# 513.net
KiCad netlist of a schematic drawn in Altium Designer
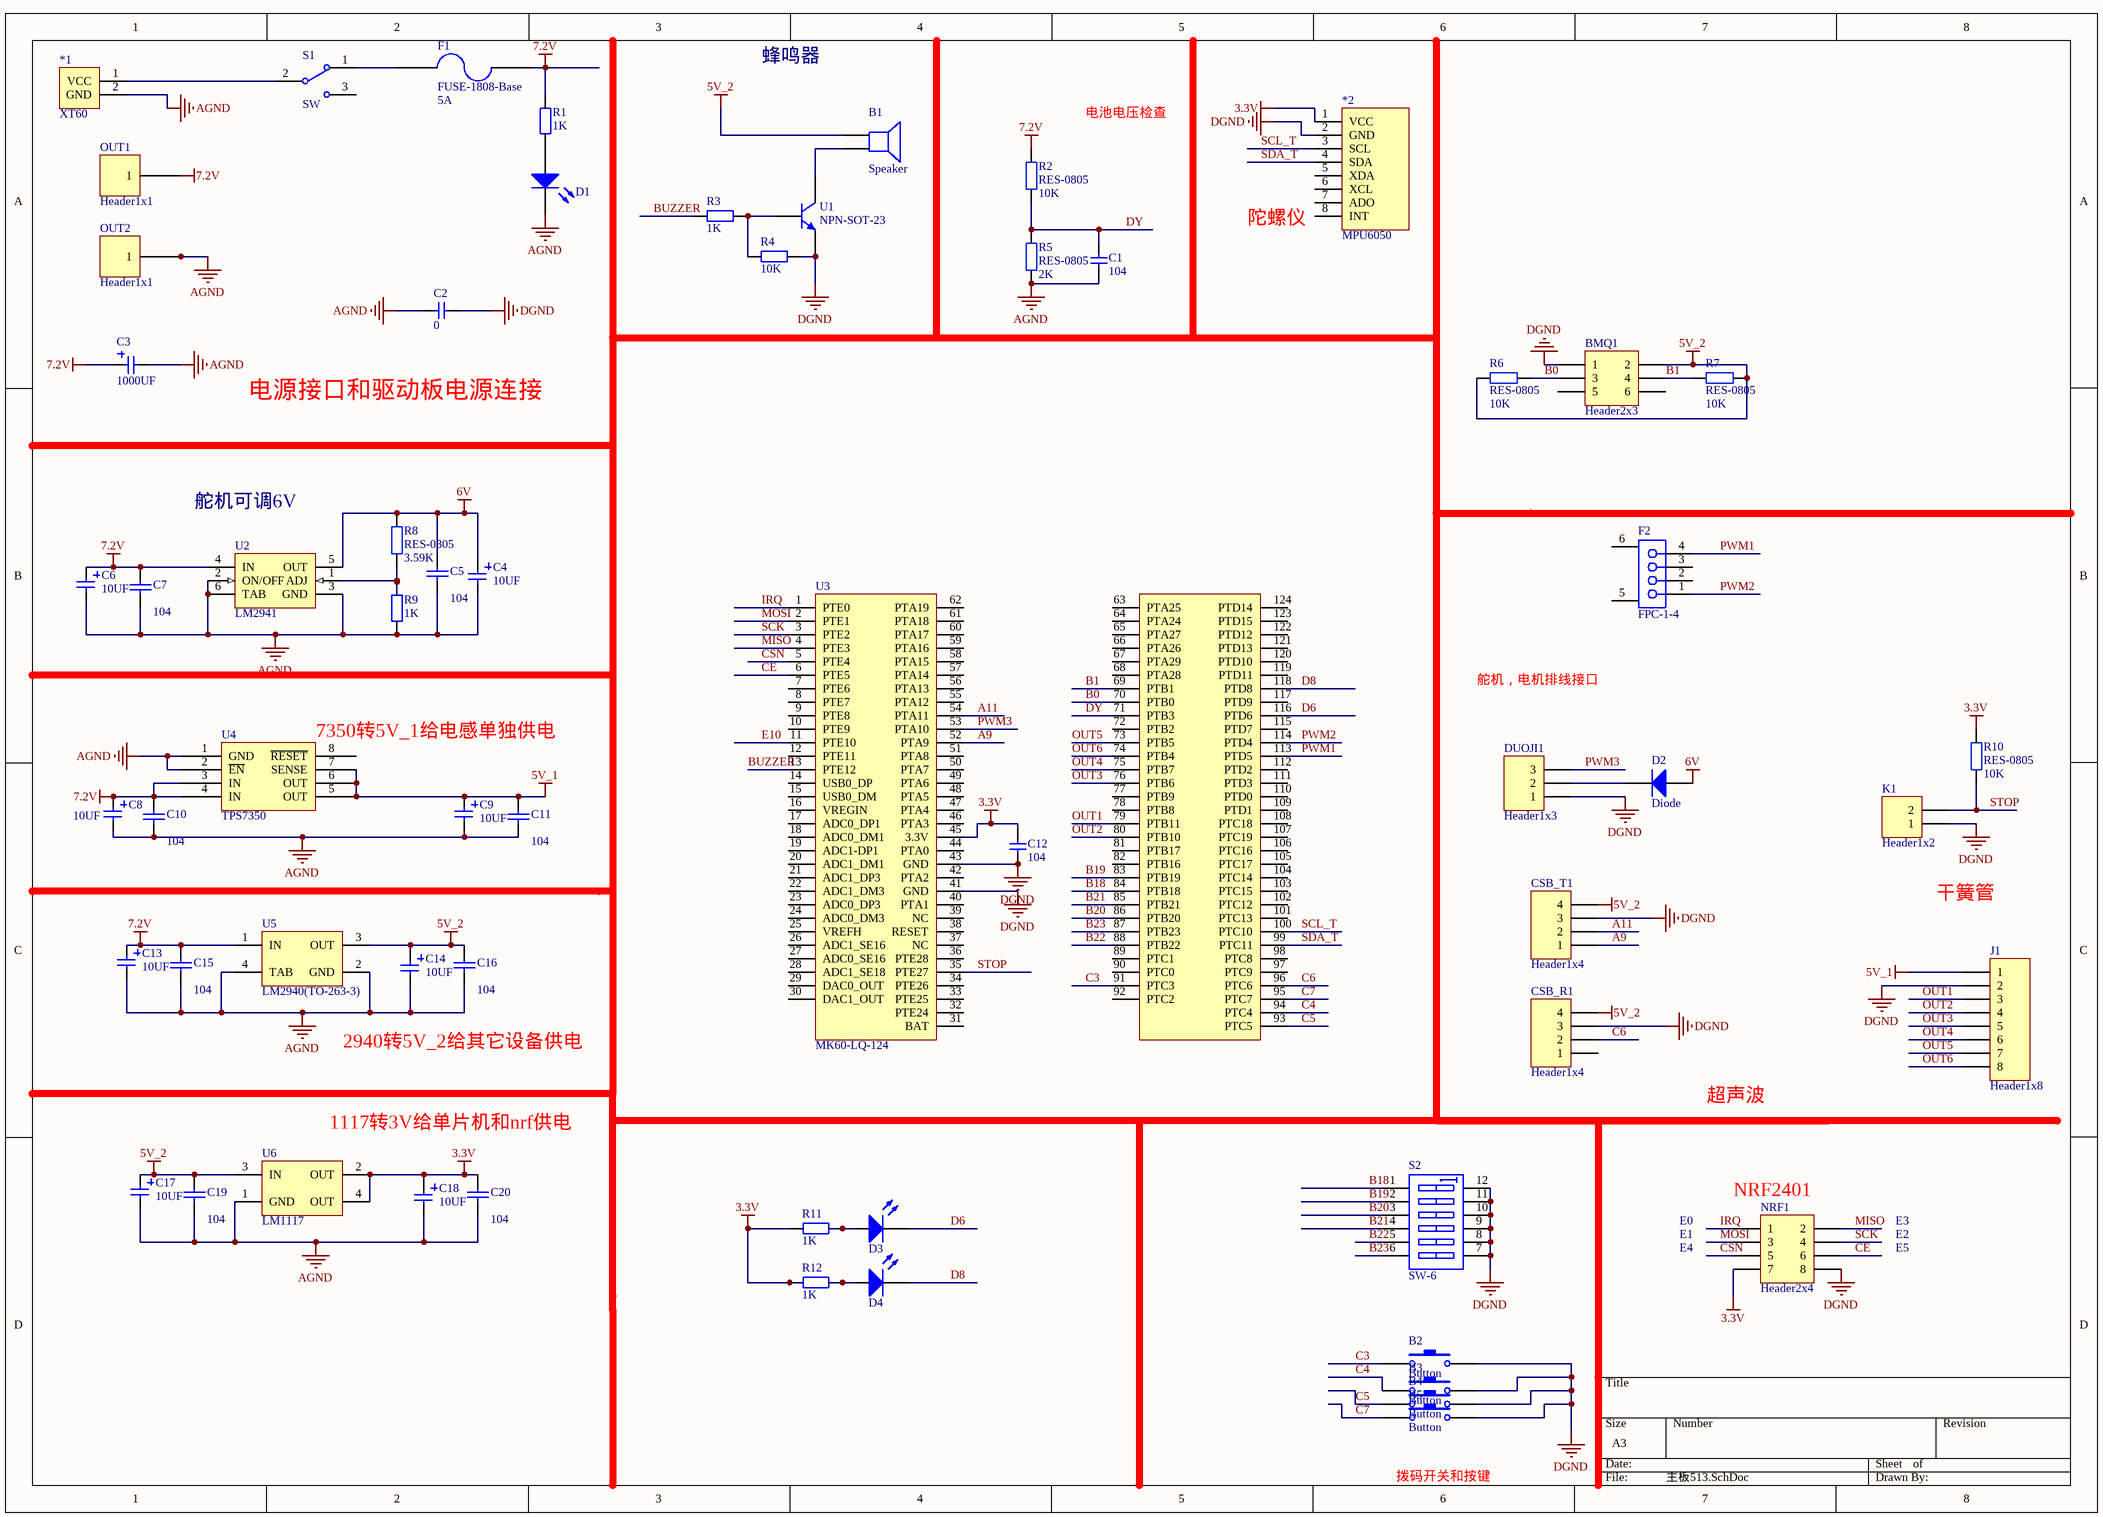
[diagram p0: 主板513.SchDoc]

(export (version "E")
  (design (tool "Eeschema 10.0.6"))
  (components
    (comp (ref "*1") (value "XT60") (footprint "XT60") (libsource (lib "信标主板") (part "XT60")))
    (comp (ref "*2") (value "MPU6050") (footprint "MPU6050") (libsource (lib "光电主板") (part "MPU6050")))
    (comp (ref "B1")
      (value "Speaker")
      (footprint "Beep")
      (description "Loudspeaker")
      (fields (field (name "PUBLISHER") "Altium Limited"))
      (libsource (lib "光电主板") (part "Speaker"))
    )
    (comp (ref "B2") (value "Button") (footprint "Button-SMT") (libsource (lib "Common_XJP") (part "Button")))
    (comp (ref "B3") (value "Button") (footprint "Button-SMT") (libsource (lib "Common_XJP") (part "Button")))
    (comp (ref "B4") (value "Button") (footprint "Button-SMT") (libsource (lib "Common_XJP") (part "Button")))
    (comp (ref "B5") (value "Button") (footprint "Button-SMT") (libsource (lib "Common_XJP") (part "Button")))
    (comp (ref "BMQ1")
      (value "Header2x3")
      (footprint "HEADER2X3")
      (libsource (lib "KING_Connector") (part "Header2x3"))
    )
    (comp (ref "C1")
      (value "CAP_0805")
      (footprint "C0805")
      (fields (field (name "ALTIUM_UNNAMED_1") "104"))
      (libsource (lib "主板2017") (part "CAP_0805"))
    )
    (comp (ref "C2")
      (value "CAP_0805")
      (footprint "C0805")
      (fields (field (name "ALTIUM_UNNAMED_1") "0"))
      (libsource (lib "KING_Common") (part "CAP_0805"))
    )
    (comp (ref "C3")
      (value "CAP_1000UF_DIP")
      (footprint "CAP_DIP_8×14")
      (fields (field (name "ALTIUM_UNNAMED_1") "1000UF"))
      (libsource (lib "KING_Common") (part "CAP_1000UF_DIP"))
    )
    (comp (ref "C4")
      (value "CAP_6032")
      (footprint "CAP_6032_C")
      (fields (field (name "ALTIUM_UNNAMED_1") "10UF"))
      (libsource (lib "KING_Common") (part "CAP_6032"))
    )
    (comp (ref "C5")
      (value "~")
      (footprint "CAP-0805")
      (fields (field (name "ALTIUM_UNNAMED_1") "104"))
      (libsource (lib "3.0Common_XJP") (part "CAP-0805(2012)"))
    )
    (comp (ref "C6")
      (value "CAP_6032")
      (footprint "CAP_6032_C")
      (fields (field (name "ALTIUM_UNNAMED_1") "10UF"))
      (libsource (lib "KING_Common") (part "CAP_6032"))
    )
    (comp (ref "C7")
      (value "~")
      (footprint "CAP-0805")
      (fields (field (name "ALTIUM_UNNAMED_1") "104"))
      (libsource (lib "3.0Common_XJP") (part "CAP-0805(2012)"))
    )
    (comp (ref "C8")
      (value "CAP_6032")
      (footprint "CAP_6032_C")
      (fields (field (name "ALTIUM_UNNAMED_1") "10UF"))
      (libsource (lib "KING_Common") (part "CAP_6032"))
    )
    (comp (ref "C9")
      (value "CAP_6032")
      (footprint "CAP_6032_C")
      (fields (field (name "ALTIUM_UNNAMED_1") "10UF"))
      (libsource (lib "KING_Common") (part "CAP_6032"))
    )
    (comp (ref "C10")
      (value "~")
      (footprint "CAP-0805")
      (fields (field (name "ALTIUM_UNNAMED_1") "104"))
      (libsource (lib "3.0Common_XJP") (part "CAP-0805(2012)"))
    )
    (comp (ref "C11")
      (value "~")
      (footprint "CAP-0805")
      (fields (field (name "ALTIUM_UNNAMED_1") "104"))
      (libsource (lib "3.0Common_XJP") (part "CAP-0805(2012)"))
    )
    (comp (ref "C12")
      (value "CAP_0805")
      (footprint "C0805")
      (fields (field (name "ALTIUM_UNNAMED_1") "104"))
      (libsource (lib "KING_Common") (part "CAP_0805"))
    )
    (comp (ref "C13")
      (value "CAP_6032")
      (footprint "CAP_6032_C")
      (fields (field (name "ALTIUM_UNNAMED_1") "10UF"))
      (libsource (lib "KING_Common") (part "CAP_6032"))
    )
    (comp (ref "C14")
      (value "CAP_6032")
      (footprint "CAP_6032_C")
      (fields (field (name "ALTIUM_UNNAMED_1") "10UF"))
      (libsource (lib "KING_Common") (part "CAP_6032"))
    )
    (comp (ref "C15")
      (value "~")
      (footprint "CAP-0805")
      (fields (field (name "ALTIUM_UNNAMED_1") "104"))
      (libsource (lib "3.0Common_XJP") (part "CAP-0805(2012)"))
    )
    (comp (ref "C16")
      (value "~")
      (footprint "CAP-0805")
      (fields (field (name "ALTIUM_UNNAMED_1") "104"))
      (libsource (lib "3.0Common_XJP") (part "CAP-0805(2012)"))
    )
    (comp (ref "C17")
      (value "CAP_6032")
      (footprint "CAP_6032_C")
      (fields (field (name "ALTIUM_UNNAMED_1") "10UF"))
      (libsource (lib "KING_Common") (part "CAP_6032"))
    )
    (comp (ref "C18")
      (value "CAP_6032")
      (footprint "CAP_6032_C")
      (fields (field (name "ALTIUM_UNNAMED_1") "10UF"))
      (libsource (lib "KING_Common") (part "CAP_6032"))
    )
    (comp (ref "C19")
      (value "~")
      (footprint "CAP-0805")
      (fields (field (name "ALTIUM_UNNAMED_1") "104"))
      (libsource (lib "3.0Common_XJP") (part "CAP-0805(2012)"))
    )
    (comp (ref "C20")
      (value "~")
      (footprint "CAP-0805")
      (fields (field (name "ALTIUM_UNNAMED_1") "104"))
      (libsource (lib "3.0Common_XJP") (part "CAP-0805(2012)"))
    )
    (comp (ref "CSB_R1")
      (value "Header1x4")
      (footprint "HEADER1X4")
      (libsource (lib "KING_Connector") (part "Header1x4"))
    )
    (comp (ref "CSB_T1")
      (value "Header1x4")
      (footprint "HEADER1X4")
      (libsource (lib "KING_Connector") (part "Header1x4"))
    )
    (comp (ref "D1")
      (value "LED_0805_R")
      (footprint "LED_0805_R")
      (libsource (lib "KING_Common") (part "LED_0805_R"))
    )
    (comp (ref "D2") (value "Diode") (footprint "DIODE") (libsource (lib "ZYF_Common") (part "Diode")))
    (comp (ref "D3")
      (value "LED_0805_R")
      (footprint "LED_0805_R")
      (libsource (lib "KING_Common") (part "LED_0805_R"))
    )
    (comp (ref "D4")
      (value "LED_0805_R")
      (footprint "LED_0805_R")
      (libsource (lib "KING_Common") (part "LED_0805_R"))
    )
    (comp (ref "DUOJI1")
      (value "Header1x3")
      (footprint "HEADER1X3")
      (libsource (lib "ZYF_Connector") (part "Header1x3"))
    )
    (comp (ref "F1")
      (value "FUSE-1808-Base")
      (footprint "Fuse1808_Base")
      (description "保险丝")
      (fields (field (name "ALTIUM_UNNAMED_1") "5A"))
      (libsource (lib "电机驱动") (part "FUSE-1808-Base"))
    )
    (comp (ref "F2")
      (value "FPC-1-4")
      (footprint "FPC-1-4")
      (libsource (lib "ZYF_Connector") (part "FPC-1-4"))
    )
    (comp (ref "J1")
      (value "Header1x8")
      (footprint "HEADER1X8")
      (libsource (lib "KING_Connector") (part "Header1x8"))
    )
    (comp (ref "K1")
      (value "Header1x2")
      (footprint "HEADER1X2")
      (libsource (lib "KING_Connector") (part "Header1x2"))
    )
    (comp (ref "NRF1")
      (value "Header2x4")
      (footprint "HEADER2X4")
      (libsource (lib "KING_Connector") (part "Header2x4"))
    )
    (comp (ref "OUT1")
      (value "Header1x1")
      (footprint "HEADER1X1")
      (libsource (lib "ZZY_connector") (part "Header1x1"))
    )
    (comp (ref "OUT2")
      (value "Header1x1")
      (footprint "HEADER1X1")
      (libsource (lib "ZZY_connector") (part "Header1x1"))
    )
    (comp (ref "R1")
      (value "RES")
      (footprint "R0805")
      (fields (field (name "ALTIUM_UNNAMED_1") "1K"))
      (libsource (lib "KING_Common") (part "RES"))
    )
    (comp (ref "R2")
      (value "RES-0805")
      (footprint "RES-0805")
      (fields (field (name "ALTIUM_UNNAMED_1") "10K"))
      (libsource (lib "主板2017") (part "RES-0805"))
    )
    (comp (ref "R3")
      (value "RES")
      (footprint "R0805")
      (fields (field (name "ALTIUM_UNNAMED_1") "1K"))
      (libsource (lib "KING_Common") (part "RES"))
    )
    (comp (ref "R4")
      (value "RES")
      (footprint "R0805")
      (fields (field (name "ALTIUM_UNNAMED_1") "10K"))
      (libsource (lib "KING_Common") (part "RES"))
    )
    (comp (ref "R5")
      (value "RES-0805")
      (footprint "RES-0805")
      (fields (field (name "ALTIUM_UNNAMED_1") "2K"))
      (libsource (lib "主板2017") (part "RES-0805"))
    )
    (comp (ref "R6")
      (value "RES-0805")
      (footprint "RES-0805")
      (fields (field (name "ALTIUM_UNNAMED_1") "10K"))
      (libsource (lib "Common_XJP") (part "RES-0805"))
    )
    (comp (ref "R7")
      (value "RES-0805")
      (footprint "RES-0805")
      (fields (field (name "ALTIUM_UNNAMED_1") "10K"))
      (libsource (lib "Common_XJP") (part "RES-0805"))
    )
    (comp (ref "R8")
      (value "RES-0805")
      (footprint "RES-0805")
      (fields (field (name "ALTIUM_UNNAMED_1") "3.59K"))
      (libsource (lib "TQH_common") (part "RES-0805"))
    )
    (comp (ref "R9")
      (value "RES")
      (footprint "R0805")
      (fields (field (name "ALTIUM_UNNAMED_1") "1K"))
      (libsource (lib "KING_Common") (part "RES"))
    )
    (comp (ref "R10")
      (value "RES-0805")
      (footprint "RES-0805")
      (fields (field (name "ALTIUM_UNNAMED_1") "10K"))
      (libsource (lib "Common_XJP") (part "RES-0805"))
    )
    (comp (ref "R11")
      (value "RES")
      (footprint "R0805")
      (fields (field (name "ALTIUM_UNNAMED_1") "1K"))
      (libsource (lib "KING_Common") (part "RES"))
    )
    (comp (ref "R12")
      (value "RES")
      (footprint "R0805")
      (fields (field (name "ALTIUM_UNNAMED_1") "1K"))
      (libsource (lib "KING_Common") (part "RES"))
    )
    (comp (ref "S1") (value "SW") (footprint "SW-B") (libsource (lib "Common_XJP") (part "SW")))
    (comp (ref "S2") (value "SW-6") (footprint "SW-SMT-12") (libsource (lib "Common_XJP") (part "SW-6")))
    (comp (ref "U1")
      (value "NPN-SOT-23")
      (footprint "SOT-23")
      (libsource (lib "Common_XJP") (part "NPN-SOT-23"))
    )
    (comp (ref "U2") (value "LM2941") (footprint "TO-263-5S") (libsource (lib "KING_IC") (part "LM2941")))
    (comp (ref "U3")
      (value "MK60-LQ-124")
      (footprint "MK60-LQ-144")
      (libsource (lib "IC_XJP") (part "MK60-LQ-124"))
    )
    (comp (ref "U4") (value "TPS7350") (footprint "SOP-8") (libsource (lib "ZYF_IC") (part "TPS7350")))
    (comp (ref "U5")
      (value "LM2940(TO-263-3)")
      (footprint "TO-263-3")
      (libsource (lib "ZYF_IC") (part "LM2940(TO-263-3)"))
    )
    (comp (ref "U6")
      (value "LM1117")
      (footprint "SOT-223")
      (libsource (lib "KING_IC") (part "LM1117_SOT_223"))
    )
  )
  (nets
    (net (code "1") (name "/A9") (class "Default")
      (node (ref "CSB_T1") (pin "1") (pinfunction "1_1") (pintype "passive"))
      (node (ref "U3") (pin "52") (pinfunction "PTA9_52") (pintype "passive"))
    )
    (net (code "2") (name "/A11") (class "Default")
      (node (ref "CSB_T1") (pin "2") (pinfunction "2_2") (pintype "passive"))
      (node (ref "U3") (pin "54") (pinfunction "PTA11_54") (pintype "passive"))
    )
    (net (code "3") (name "/B0") (class "Default")
      (node (ref "BMQ1") (pin "3") (pinfunction "3_3") (pintype "passive"))
      (node (ref "R6") (pin "2") (pinfunction "2_2") (pintype "passive"))
      (node (ref "U3") (pin "70") (pinfunction "PTB0_70") (pintype "passive"))
    )
    (net (code "4") (name "/B1") (class "Default")
      (node (ref "BMQ1") (pin "4") (pinfunction "4_4") (pintype "passive"))
      (node (ref "R7") (pin "1") (pinfunction "1_1") (pintype "passive"))
      (node (ref "U3") (pin "69") (pinfunction "PTB1_69") (pintype "passive"))
    )
    (net (code "5") (name "/B18") (class "Default")
      (node (ref "S2") (pin "1") (pinfunction "A1_1") (pintype "passive"))
      (node (ref "U3") (pin "84") (pinfunction "PTB18_84") (pintype "passive"))
    )
    (net (code "6") (name "/B19") (class "Default")
      (node (ref "S2") (pin "2") (pinfunction "A2_2") (pintype "passive"))
      (node (ref "U3") (pin "83") (pinfunction "PTB19_83") (pintype "passive"))
    )
    (net (code "7") (name "/B20") (class "Default")
      (node (ref "S2") (pin "3") (pinfunction "A3_3") (pintype "passive"))
      (node (ref "U3") (pin "86") (pinfunction "PTB20_86") (pintype "passive"))
    )
    (net (code "8") (name "/B21") (class "Default")
      (node (ref "S2") (pin "4") (pinfunction "A4_4") (pintype "passive"))
      (node (ref "U3") (pin "85") (pinfunction "PTB21_85") (pintype "passive"))
    )
    (net (code "9") (name "/B22") (class "Default")
      (node (ref "S2") (pin "5") (pinfunction "A5_5") (pintype "passive"))
      (node (ref "U3") (pin "88") (pinfunction "PTB22_88") (pintype "passive"))
    )
    (net (code "10") (name "/B23") (class "Default")
      (node (ref "S2") (pin "6") (pinfunction "A6_6") (pintype "passive"))
      (node (ref "U3") (pin "87") (pinfunction "PTB23_87") (pintype "passive"))
    )
    (net (code "11") (name "/BUZZER") (class "Default")
      (node (ref "R3") (pin "1") (pinfunction "1_1") (pintype "passive"))
      (node (ref "U3") (pin "13") (pinfunction "PTE12_13") (pintype "passive"))
    )
    (net (code "12") (name "/C3") (class "Default")
      (node (ref "B2") (pin "1") (pinfunction "1_1") (pintype "passive"))
      (node (ref "U3") (pin "91") (pinfunction "PTC3_91") (pintype "passive"))
    )
    (net (code "13") (name "/C4") (class "Default")
      (node (ref "B3") (pin "1") (pinfunction "1_1") (pintype "passive"))
      (node (ref "U3") (pin "94") (pinfunction "PTC4_94") (pintype "passive"))
    )
    (net (code "14") (name "/C5") (class "Default")
      (node (ref "B4") (pin "1") (pinfunction "1_1") (pintype "passive"))
      (node (ref "U3") (pin "93") (pinfunction "PTC5_93") (pintype "passive"))
    )
    (net (code "15") (name "/C6") (class "Default")
      (node (ref "CSB_R1") (pin "2") (pinfunction "2_2") (pintype "passive"))
      (node (ref "U3") (pin "96") (pinfunction "PTC6_96") (pintype "passive"))
    )
    (net (code "16") (name "/C7") (class "Default")
      (node (ref "B5") (pin "1") (pinfunction "1_1") (pintype "passive"))
      (node (ref "U3") (pin "95") (pinfunction "PTC7_95") (pintype "passive"))
    )
    (net (code "17") (name "/CE") (class "Default")
      (node (ref "NRF1") (pin "6") (pinfunction "6_6") (pintype "passive"))
      (node (ref "U3") (pin "6") (pinfunction "PTE5_6") (pintype "passive"))
    )
    (net (code "18") (name "/CSN") (class "Default")
      (node (ref "NRF1") (pin "5") (pinfunction "5_5") (pintype "passive"))
      (node (ref "U3") (pin "5") (pinfunction "PTE4_5") (pintype "passive"))
    )
    (net (code "19") (name "/D6") (class "Default")
      (node (ref "D3") (pin "2") (pinfunction "K_2") (pintype "passive"))
      (node (ref "U3") (pin "116") (pinfunction "PTD6_116") (pintype "passive"))
    )
    (net (code "20") (name "/D8") (class "Default")
      (node (ref "D4") (pin "2") (pinfunction "K_2") (pintype "passive"))
      (node (ref "U3") (pin "118") (pinfunction "PTD8_118") (pintype "passive"))
    )
    (net (code "21") (name "/DY") (class "Default")
      (node (ref "C1") (pin "2") (pinfunction "2_2") (pintype "passive"))
      (node (ref "R2") (pin "1") (pinfunction "1_1") (pintype "passive"))
      (node (ref "R5") (pin "2") (pinfunction "2_2") (pintype "passive"))
      (node (ref "U3") (pin "71") (pinfunction "PTB3_71") (pintype "passive"))
    )
    (net (code "22") (name "/E10") (class "Default")
      (node (ref "U3") (pin "11") (pinfunction "PTE10_11") (pintype "passive"))
    )
    (net (code "23") (name "/IRQ") (class "Default")
      (node (ref "NRF1") (pin "1") (pinfunction "1_1") (pintype "passive"))
      (node (ref "U3") (pin "1") (pinfunction "PTE0_1") (pintype "passive"))
    )
    (net (code "24") (name "/MISO") (class "Default")
      (node (ref "NRF1") (pin "2") (pinfunction "2_2") (pintype "passive"))
      (node (ref "U3") (pin "4") (pinfunction "PTE3_4") (pintype "passive"))
    )
    (net (code "25") (name "/MOSI") (class "Default")
      (node (ref "NRF1") (pin "3") (pinfunction "3_3") (pintype "passive"))
      (node (ref "U3") (pin "2") (pinfunction "PTE1_2") (pintype "passive"))
    )
    (net (code "26") (name "/OUT1") (class "Default")
      (node (ref "J1") (pin "3") (pinfunction "3_3") (pintype "passive"))
      (node (ref "U3") (pin "79") (pinfunction "PTB11_79") (pintype "passive"))
    )
    (net (code "27") (name "/OUT2") (class "Default")
      (node (ref "J1") (pin "4") (pinfunction "4_4") (pintype "passive"))
      (node (ref "U3") (pin "80") (pinfunction "PTB10_80") (pintype "passive"))
    )
    (net (code "28") (name "/OUT3") (class "Default")
      (node (ref "J1") (pin "5") (pinfunction "5_5") (pintype "passive"))
      (node (ref "U3") (pin "76") (pinfunction "PTB6_76") (pintype "passive"))
    )
    (net (code "29") (name "/OUT4") (class "Default")
      (node (ref "J1") (pin "6") (pinfunction "6_6") (pintype "passive"))
      (node (ref "U3") (pin "75") (pinfunction "PTB7_75") (pintype "passive"))
    )
    (net (code "30") (name "/OUT5") (class "Default")
      (node (ref "J1") (pin "7") (pinfunction "7_7") (pintype "passive"))
      (node (ref "U3") (pin "73") (pinfunction "PTB5_73") (pintype "passive"))
    )
    (net (code "31") (name "/OUT6") (class "Default")
      (node (ref "J1") (pin "8") (pinfunction "8_8") (pintype "passive"))
      (node (ref "U3") (pin "74") (pinfunction "PTB4_74") (pintype "passive"))
    )
    (net (code "32") (name "/PWM1") (class "Default")
      (node (ref "F2") (pin "4") (pinfunction "4_4") (pintype "passive"))
      (node (ref "U3") (pin "113") (pinfunction "PTD5_113") (pintype "passive"))
    )
    (net (code "33") (name "/PWM2") (class "Default")
      (node (ref "F2") (pin "1") (pinfunction "1_1") (pintype "passive"))
      (node (ref "U3") (pin "114") (pinfunction "PTD4_114") (pintype "passive"))
    )
    (net (code "34") (name "/PWM3") (class "Default")
      (node (ref "DUOJI1") (pin "3") (pinfunction "3_3") (pintype "passive"))
      (node (ref "U3") (pin "53") (pinfunction "PTA10_53") (pintype "passive"))
    )
    (net (code "35") (name "/SCK") (class "Default")
      (node (ref "NRF1") (pin "4") (pinfunction "4_4") (pintype "passive"))
      (node (ref "U3") (pin "3") (pinfunction "PTE2_3") (pintype "passive"))
    )
    (net (code "36") (name "/SCL_T") (class "Default")
      (node (ref "*2") (pin "3") (pinfunction "SCL_3") (pintype "passive"))
      (node (ref "U3") (pin "100") (pinfunction "PTC10_100") (pintype "passive"))
    )
    (net (code "37") (name "/SDA_T") (class "Default")
      (node (ref "*2") (pin "4") (pinfunction "SDA_4") (pintype "passive"))
      (node (ref "U3") (pin "99") (pinfunction "PTC11_99") (pintype "passive"))
    )
    (net (code "38") (name "/STOP") (class "Default")
      (node (ref "K1") (pin "2") (pinfunction "2_2") (pintype "passive"))
      (node (ref "R10") (pin "1") (pinfunction "1_1") (pintype "passive"))
      (node (ref "U3") (pin "35") (pinfunction "PTE27_35") (pintype "passive"))
    )
    (net (code "39") (name "3.3V") (class "Default")
      (node (ref "*2") (pin "1") (pinfunction "VCC_1") (pintype "passive"))
      (node (ref "C12") (pin "2") (pinfunction "2_2") (pintype "passive"))
      (node (ref "C18") (pin "1") (pinfunction "1_1") (pintype "passive"))
      (node (ref "C20") (pin "2") (pinfunction "2_2") (pintype "passive"))
      (node (ref "NRF1") (pin "7") (pinfunction "7_7") (pintype "passive"))
      (node (ref "R10") (pin "2") (pinfunction "2_2") (pintype "passive"))
      (node (ref "R11") (pin "1") (pinfunction "1_1") (pintype "passive"))
      (node (ref "R12") (pin "1") (pinfunction "1_1") (pintype "passive"))
      (node (ref "U3") (pin "45") (pinfunction "3.3V_45") (pintype "passive"))
      (node (ref "U6") (pin "2") (pinfunction "OUT_2") (pintype "power_in"))
      (node (ref "U6") (pin "4") (pinfunction "OUT_4") (pintype "power_in"))
    )
    (net (code "40") (name "5V_1") (class "Default")
      (node (ref "C11") (pin "2") (pinfunction "2_2") (pintype "passive"))
      (node (ref "C9") (pin "1") (pinfunction "1_1") (pintype "passive"))
      (node (ref "J1") (pin "1") (pinfunction "1_1") (pintype "passive"))
      (node (ref "U4") (pin "5") (pinfunction "OUT_5") (pintype "passive"))
      (node (ref "U4") (pin "6") (pinfunction "OUT_6") (pintype "passive"))
      (node (ref "U4") (pin "7") (pinfunction "SENSE_7") (pintype "passive"))
    )
    (net (code "41") (name "5V_2") (class "Default")
      (node (ref "B1") (pin "1") (pinfunction "1_1") (pintype "passive"))
      (node (ref "BMQ1") (pin "2") (pinfunction "2_2") (pintype "passive"))
      (node (ref "C14") (pin "1") (pinfunction "1_1") (pintype "passive"))
      (node (ref "C16") (pin "2") (pinfunction "2_2") (pintype "passive"))
      (node (ref "C17") (pin "1") (pinfunction "1_1") (pintype "passive"))
      (node (ref "C19") (pin "2") (pinfunction "2_2") (pintype "passive"))
      (node (ref "CSB_R1") (pin "4") (pinfunction "4_4") (pintype "passive"))
      (node (ref "CSB_T1") (pin "4") (pinfunction "4_4") (pintype "passive"))
      (node (ref "R6") (pin "1") (pinfunction "1_1") (pintype "passive"))
      (node (ref "R7") (pin "2") (pinfunction "2_2") (pintype "passive"))
      (node (ref "U5") (pin "3") (pinfunction "OUT_3") (pintype "power_in"))
      (node (ref "U6") (pin "3") (pinfunction "IN_3") (pintype "power_in"))
    )
    (net (code "42") (name "6V") (class "Default")
      (node (ref "C4") (pin "1") (pinfunction "1_1") (pintype "passive"))
      (node (ref "C5") (pin "2") (pinfunction "2_2") (pintype "passive"))
      (node (ref "D2") (pin "1") (pinfunction "A_1") (pintype "passive"))
      (node (ref "R8") (pin "1") (pinfunction "1_1") (pintype "passive"))
      (node (ref "U2") (pin "5") (pinfunction "OUT_5") (pintype "power_in"))
    )
    (net (code "43") (name "7.2V") (class "Default")
      (node (ref "C10") (pin "2") (pinfunction "2_2") (pintype "passive"))
      (node (ref "C13") (pin "1") (pinfunction "1_1") (pintype "passive"))
      (node (ref "C15") (pin "2") (pinfunction "2_2") (pintype "passive"))
      (node (ref "C3") (pin "1") (pinfunction "1_1") (pintype "passive"))
      (node (ref "C6") (pin "1") (pinfunction "1_1") (pintype "passive"))
      (node (ref "C7") (pin "2") (pinfunction "2_2") (pintype "passive"))
      (node (ref "C8") (pin "1") (pinfunction "1_1") (pintype "passive"))
      (node (ref "F1") (pin "2") (pinfunction "2_2") (pintype "passive"))
      (node (ref "OUT1") (pin "1") (pinfunction "1_1") (pintype "passive"))
      (node (ref "R1") (pin "1") (pinfunction "1_1") (pintype "passive"))
      (node (ref "R2") (pin "2") (pinfunction "2_2") (pintype "passive"))
      (node (ref "U2") (pin "4") (pinfunction "IN_4") (pintype "power_in"))
      (node (ref "U4") (pin "3") (pinfunction "IN_3") (pintype "passive"))
      (node (ref "U4") (pin "4") (pinfunction "IN_4") (pintype "passive"))
      (node (ref "U5") (pin "1") (pinfunction "IN_1") (pintype "power_in"))
    )
    (net (code "44") (name "AGND") (class "Default")
      (node (ref "*1") (pin "2") (pinfunction "GND_2") (pintype "passive"))
      (node (ref "C1") (pin "1") (pinfunction "1_1") (pintype "passive"))
      (node (ref "C10") (pin "1") (pinfunction "1_1") (pintype "passive"))
      (node (ref "C11") (pin "1") (pinfunction "1_1") (pintype "passive"))
      (node (ref "C13") (pin "2") (pinfunction "2_2") (pintype "passive"))
      (node (ref "C14") (pin "2") (pinfunction "2_2") (pintype "passive"))
      (node (ref "C15") (pin "1") (pinfunction "1_1") (pintype "passive"))
      (node (ref "C16") (pin "1") (pinfunction "1_1") (pintype "passive"))
      (node (ref "C17") (pin "2") (pinfunction "2_2") (pintype "passive"))
      (node (ref "C18") (pin "2") (pinfunction "2_2") (pintype "passive"))
      (node (ref "C19") (pin "1") (pinfunction "1_1") (pintype "passive"))
      (node (ref "C2") (pin "2") (pinfunction "2_2") (pintype "passive"))
      (node (ref "C20") (pin "1") (pinfunction "1_1") (pintype "passive"))
      (node (ref "C3") (pin "2") (pinfunction "2_2") (pintype "passive"))
      (node (ref "C4") (pin "2") (pinfunction "2_2") (pintype "passive"))
      (node (ref "C5") (pin "1") (pinfunction "1_1") (pintype "passive"))
      (node (ref "C6") (pin "2") (pinfunction "2_2") (pintype "passive"))
      (node (ref "C7") (pin "1") (pinfunction "1_1") (pintype "passive"))
      (node (ref "C8") (pin "2") (pinfunction "2_2") (pintype "passive"))
      (node (ref "C9") (pin "2") (pinfunction "2_2") (pintype "passive"))
      (node (ref "D1") (pin "2") (pinfunction "K_2") (pintype "passive"))
      (node (ref "OUT2") (pin "1") (pinfunction "1_1") (pintype "passive"))
      (node (ref "R5") (pin "1") (pinfunction "1_1") (pintype "passive"))
      (node (ref "R9") (pin "1") (pinfunction "1_1") (pintype "passive"))
      (node (ref "U2") (pin "2") (pinfunction "ON/OFF_2") (pintype "input"))
      (node (ref "U2") (pin "3") (pinfunction "GND_3") (pintype "power_in"))
      (node (ref "U2") (pin "6") (pinfunction "TAB_6") (pintype "power_in"))
      (node (ref "U4") (pin "1") (pinfunction "GND_1") (pintype "passive"))
      (node (ref "U4") (pin "2") (pinfunction "~{EN}_2") (pintype "passive"))
      (node (ref "U5") (pin "2") (pinfunction "GND_2") (pintype "power_in"))
      (node (ref "U5") (pin "4") (pinfunction "TAB_4") (pintype "power_in"))
      (node (ref "U6") (pin "1") (pinfunction "GND_1") (pintype "power_in"))
    )
    (net (code "45") (name "DGND") (class "Default")
      (node (ref "*2") (pin "2") (pinfunction "GND_2") (pintype "passive"))
      (node (ref "B2") (pin "2") (pinfunction "2_2") (pintype "passive"))
      (node (ref "B3") (pin "2") (pinfunction "2_2") (pintype "passive"))
      (node (ref "B4") (pin "2") (pinfunction "2_2") (pintype "passive"))
      (node (ref "B5") (pin "2") (pinfunction "2_2") (pintype "passive"))
      (node (ref "BMQ1") (pin "1") (pinfunction "1_1") (pintype "passive"))
      (node (ref "C12") (pin "1") (pinfunction "1_1") (pintype "passive"))
      (node (ref "C2") (pin "1") (pinfunction "1_1") (pintype "passive"))
      (node (ref "CSB_R1") (pin "3") (pinfunction "3_3") (pintype "passive"))
      (node (ref "CSB_T1") (pin "3") (pinfunction "3_3") (pintype "passive"))
      (node (ref "DUOJI1") (pin "1") (pinfunction "1_1") (pintype "passive"))
      (node (ref "J1") (pin "2") (pinfunction "2_2") (pintype "passive"))
      (node (ref "K1") (pin "1") (pinfunction "1_1") (pintype "passive"))
      (node (ref "NRF1") (pin "8") (pinfunction "8_8") (pintype "passive"))
      (node (ref "R4") (pin "2") (pinfunction "2_2") (pintype "passive"))
      (node (ref "S2") (pin "10") (pinfunction "B3_10") (pintype "passive"))
      (node (ref "S2") (pin "11") (pinfunction "B2_11") (pintype "passive"))
      (node (ref "S2") (pin "12") (pinfunction "B1_12") (pintype "passive"))
      (node (ref "S2") (pin "7") (pinfunction "B6_7") (pintype "passive"))
      (node (ref "S2") (pin "8") (pinfunction "B5_8") (pintype "passive"))
      (node (ref "S2") (pin "9") (pinfunction "B4_9") (pintype "passive"))
      (node (ref "U1") (pin "1") (pinfunction "E_1") (pintype "passive"))
      (node (ref "U3") (pin "41") (pinfunction "GND_41") (pintype "passive"))
      (node (ref "U3") (pin "43") (pinfunction "GND_43") (pintype "passive"))
    )
    (net (code "46") (name "Net-(*1-VCC)") (class "Default")
      (node (ref "*1") (pin "1") (pinfunction "VCC_1") (pintype "passive"))
      (node (ref "S1") (pin "2") (pinfunction "2_2") (pintype "passive"))
    )
    (net (code "47") (name "Net-(D1-A)") (class "Default")
      (node (ref "D1") (pin "1") (pinfunction "A_1") (pintype "passive"))
      (node (ref "R1") (pin "2") (pinfunction "2_2") (pintype "passive"))
    )
    (net (code "48") (name "Net-(D2-K)") (class "Default")
      (node (ref "D2") (pin "2") (pinfunction "K_2") (pintype "passive"))
      (node (ref "DUOJI1") (pin "2") (pinfunction "2_2") (pintype "passive"))
    )
    (net (code "49") (name "Net-(D3-A)") (class "Default")
      (node (ref "D3") (pin "1") (pinfunction "A_1") (pintype "passive"))
      (node (ref "R11") (pin "2") (pinfunction "2_2") (pintype "passive"))
    )
    (net (code "50") (name "Net-(D4-A)") (class "Default")
      (node (ref "D4") (pin "1") (pinfunction "A_1") (pintype "passive"))
      (node (ref "R12") (pin "2") (pinfunction "2_2") (pintype "passive"))
    )
    (net (code "51") (name "Net-(F1-Pad1)") (class "Default")
      (node (ref "F1") (pin "1") (pinfunction "1_1") (pintype "passive"))
      (node (ref "S1") (pin "1") (pinfunction "1_1") (pintype "passive"))
    )
    (net (code "52") (name "Net-(U1-B)") (class "Default")
      (node (ref "R3") (pin "2") (pinfunction "2_2") (pintype "passive"))
      (node (ref "R4") (pin "1") (pinfunction "1_1") (pintype "passive"))
      (node (ref "U1") (pin "2") (pinfunction "B_2") (pintype "passive"))
    )
    (net (code "53") (name "Net-(U1-C)") (class "Default")
      (node (ref "B1") (pin "2") (pinfunction "2_2") (pintype "passive"))
      (node (ref "U1") (pin "3") (pinfunction "C_3") (pintype "passive"))
    )
    (net (code "54") (name "Net-(U2-ADJ)") (class "Default")
      (node (ref "R8") (pin "2") (pinfunction "2_2") (pintype "passive"))
      (node (ref "R9") (pin "2") (pinfunction "2_2") (pintype "passive"))
      (node (ref "U2") (pin "1") (pinfunction "ADJ_1") (pintype "input"))
    )
    (net (code "55") (name "unconnected-(*2-ADO-Pad7)") (class "Default")
      (node (ref "*2") (pin "7") (pinfunction "ADO_7") (pintype "passive"))
    )
    (net (code "56") (name "unconnected-(*2-INT-Pad8)") (class "Default")
      (node (ref "*2") (pin "8") (pinfunction "INT_8") (pintype "passive"))
    )
    (net (code "57") (name "unconnected-(*2-XCL-Pad6)") (class "Default")
      (node (ref "*2") (pin "6") (pinfunction "XCL_6") (pintype "passive"))
    )
    (net (code "58") (name "unconnected-(*2-XDA-Pad5)") (class "Default")
      (node (ref "*2") (pin "5") (pinfunction "XDA_5") (pintype "passive"))
    )
    (net (code "59") (name "unconnected-(BMQ1-Pad5)") (class "Default")
      (node (ref "BMQ1") (pin "5") (pinfunction "5_5") (pintype "passive"))
    )
    (net (code "60") (name "unconnected-(BMQ1-Pad6)") (class "Default")
      (node (ref "BMQ1") (pin "6") (pinfunction "6_6") (pintype "passive"))
    )
    (net (code "61") (name "unconnected-(CSB_R1-Pad1)") (class "Default")
      (node (ref "CSB_R1") (pin "1") (pinfunction "1_1") (pintype "passive"))
    )
    (net (code "62") (name "unconnected-(F2-MH1-Pad5)") (class "Default")
      (node (ref "F2") (pin "5") (pinfunction "MH1_5") (pintype "passive"))
    )
    (net (code "63") (name "unconnected-(F2-MH2-Pad6)") (class "Default")
      (node (ref "F2") (pin "6") (pinfunction "MH2_6") (pintype "passive"))
    )
    (net (code "64") (name "unconnected-(F2-Pad2)") (class "Default")
      (node (ref "F2") (pin "2") (pinfunction "2_2") (pintype "passive"))
    )
    (net (code "65") (name "unconnected-(F2-Pad3)") (class "Default")
      (node (ref "F2") (pin "3") (pinfunction "3_3") (pintype "passive"))
    )
    (net (code "66") (name "unconnected-(S1-Pad3)") (class "Default")
      (node (ref "S1") (pin "3") (pinfunction "3_3") (pintype "passive"))
    )
    (net (code "67") (name "unconnected-(U3-ADC0_DM1-Pad18)") (class "Default")
      (node (ref "U3") (pin "18") (pinfunction "ADC0_DM1_18") (pintype "passive"))
    )
    (net (code "68") (name "unconnected-(U3-ADC0_DM3-Pad24)") (class "Default")
      (node (ref "U3") (pin "24") (pinfunction "ADC0_DM3_24") (pintype "passive"))
    )
    (net (code "69") (name "unconnected-(U3-ADC0_DP1-Pad17)") (class "Default")
      (node (ref "U3") (pin "17") (pinfunction "ADC0_DP1_17") (pintype "passive"))
    )
    (net (code "70") (name "unconnected-(U3-ADC0_DP3-Pad23)") (class "Default")
      (node (ref "U3") (pin "23") (pinfunction "ADC0_DP3_23") (pintype "passive"))
    )
    (net (code "71") (name "unconnected-(U3-ADC0_SE16-Pad27)") (class "Default")
      (node (ref "U3") (pin "27") (pinfunction "ADC0_SE16_27") (pintype "passive"))
    )
    (net (code "72") (name "unconnected-(U3-ADC1-DP1-Pad19)") (class "Default")
      (node (ref "U3") (pin "19") (pinfunction "ADC1-DP1_19") (pintype "passive"))
    )
    (net (code "73") (name "unconnected-(U3-ADC1_DM1-Pad20)") (class "Default")
      (node (ref "U3") (pin "20") (pinfunction "ADC1_DM1_20") (pintype "passive"))
    )
    (net (code "74") (name "unconnected-(U3-ADC1_DM3-Pad22)") (class "Default")
      (node (ref "U3") (pin "22") (pinfunction "ADC1_DM3_22") (pintype "passive"))
    )
    (net (code "75") (name "unconnected-(U3-ADC1_DP3-Pad21)") (class "Default")
      (node (ref "U3") (pin "21") (pinfunction "ADC1_DP3_21") (pintype "passive"))
    )
    (net (code "76") (name "unconnected-(U3-ADC1_SE16-Pad26)") (class "Default")
      (node (ref "U3") (pin "26") (pinfunction "ADC1_SE16_26") (pintype "passive"))
    )
    (net (code "77") (name "unconnected-(U3-ADC1_SE18-Pad28)") (class "Default")
      (node (ref "U3") (pin "28") (pinfunction "ADC1_SE18_28") (pintype "passive"))
    )
    (net (code "78") (name "unconnected-(U3-BAT-Pad31)") (class "Default")
      (node (ref "U3") (pin "31") (pinfunction "BAT_31") (pintype "passive"))
    )
    (net (code "79") (name "unconnected-(U3-DAC0_OUT-Pad29)") (class "Default")
      (node (ref "U3") (pin "29") (pinfunction "DAC0_OUT_29") (pintype "passive"))
    )
    (net (code "80") (name "unconnected-(U3-DAC1_OUT-Pad30)") (class "Default")
      (node (ref "U3") (pin "30") (pinfunction "DAC1_OUT_30") (pintype "passive"))
    )
    (net (code "81") (name "unconnected-(U3-NC-Pad37)") (class "Default")
      (node (ref "U3") (pin "37") (pinfunction "NC_37") (pintype "passive"))
    )
    (net (code "82") (name "unconnected-(U3-NC-Pad39)") (class "Default")
      (node (ref "U3") (pin "39") (pinfunction "NC_39") (pintype "passive"))
    )
    (net (code "83") (name "unconnected-(U3-PTA0-Pad44)") (class "Default")
      (node (ref "U3") (pin "44") (pinfunction "PTA0_44") (pintype "passive"))
    )
    (net (code "84") (name "unconnected-(U3-PTA1-Pad40)") (class "Default")
      (node (ref "U3") (pin "40") (pinfunction "PTA1_40") (pintype "passive"))
    )
    (net (code "85") (name "unconnected-(U3-PTA2-Pad42)") (class "Default")
      (node (ref "U3") (pin "42") (pinfunction "PTA2_42") (pintype "passive"))
    )
    (net (code "86") (name "unconnected-(U3-PTA3-Pad46)") (class "Default")
      (node (ref "U3") (pin "46") (pinfunction "PTA3_46") (pintype "passive"))
    )
    (net (code "87") (name "unconnected-(U3-PTA4-Pad47)") (class "Default")
      (node (ref "U3") (pin "47") (pinfunction "PTA4_47") (pintype "passive"))
    )
    (net (code "88") (name "unconnected-(U3-PTA5-Pad48)") (class "Default")
      (node (ref "U3") (pin "48") (pinfunction "PTA5_48") (pintype "passive"))
    )
    (net (code "89") (name "unconnected-(U3-PTA6-Pad49)") (class "Default")
      (node (ref "U3") (pin "49") (pinfunction "PTA6_49") (pintype "passive"))
    )
    (net (code "90") (name "unconnected-(U3-PTA7-Pad50)") (class "Default")
      (node (ref "U3") (pin "50") (pinfunction "PTA7_50") (pintype "passive"))
    )
    (net (code "91") (name "unconnected-(U3-PTA8-Pad51)") (class "Default")
      (node (ref "U3") (pin "51") (pinfunction "PTA8_51") (pintype "passive"))
    )
    (net (code "92") (name "unconnected-(U3-PTA12-Pad55)") (class "Default")
      (node (ref "U3") (pin "55") (pinfunction "PTA12_55") (pintype "passive"))
    )
    (net (code "93") (name "unconnected-(U3-PTA13-Pad56)") (class "Default")
      (node (ref "U3") (pin "56") (pinfunction "PTA13_56") (pintype "passive"))
    )
    (net (code "94") (name "unconnected-(U3-PTA14-Pad57)") (class "Default")
      (node (ref "U3") (pin "57") (pinfunction "PTA14_57") (pintype "passive"))
    )
    (net (code "95") (name "unconnected-(U3-PTA15-Pad58)") (class "Default")
      (node (ref "U3") (pin "58") (pinfunction "PTA15_58") (pintype "passive"))
    )
    (net (code "96") (name "unconnected-(U3-PTA16-Pad59)") (class "Default")
      (node (ref "U3") (pin "59") (pinfunction "PTA16_59") (pintype "passive"))
    )
    (net (code "97") (name "unconnected-(U3-PTA17-Pad60)") (class "Default")
      (node (ref "U3") (pin "60") (pinfunction "PTA17_60") (pintype "passive"))
    )
    (net (code "98") (name "unconnected-(U3-PTA18-Pad61)") (class "Default")
      (node (ref "U3") (pin "61") (pinfunction "PTA18_61") (pintype "passive"))
    )
    (net (code "99") (name "unconnected-(U3-PTA19-Pad62)") (class "Default")
      (node (ref "U3") (pin "62") (pinfunction "PTA19_62") (pintype "passive"))
    )
    (net (code "100") (name "unconnected-(U3-PTA24-Pad64)") (class "Default")
      (node (ref "U3") (pin "64") (pinfunction "PTA24_64") (pintype "passive"))
    )
    (net (code "101") (name "unconnected-(U3-PTA25-Pad63)") (class "Default")
      (node (ref "U3") (pin "63") (pinfunction "PTA25_63") (pintype "passive"))
    )
    (net (code "102") (name "unconnected-(U3-PTA26-Pad66)") (class "Default")
      (node (ref "U3") (pin "66") (pinfunction "PTA26_66") (pintype "passive"))
    )
    (net (code "103") (name "unconnected-(U3-PTA27-Pad65)") (class "Default")
      (node (ref "U3") (pin "65") (pinfunction "PTA27_65") (pintype "passive"))
    )
    (net (code "104") (name "unconnected-(U3-PTA28-Pad68)") (class "Default")
      (node (ref "U3") (pin "68") (pinfunction "PTA28_68") (pintype "passive"))
    )
    (net (code "105") (name "unconnected-(U3-PTA29-Pad67)") (class "Default")
      (node (ref "U3") (pin "67") (pinfunction "PTA29_67") (pintype "passive"))
    )
    (net (code "106") (name "unconnected-(U3-PTB2-Pad72)") (class "Default")
      (node (ref "U3") (pin "72") (pinfunction "PTB2_72") (pintype "passive"))
    )
    (net (code "107") (name "unconnected-(U3-PTB8-Pad78)") (class "Default")
      (node (ref "U3") (pin "78") (pinfunction "PTB8_78") (pintype "passive"))
    )
    (net (code "108") (name "unconnected-(U3-PTB9-Pad77)") (class "Default")
      (node (ref "U3") (pin "77") (pinfunction "PTB9_77") (pintype "passive"))
    )
    (net (code "109") (name "unconnected-(U3-PTB16-Pad82)") (class "Default")
      (node (ref "U3") (pin "82") (pinfunction "PTB16_82") (pintype "passive"))
    )
    (net (code "110") (name "unconnected-(U3-PTB17-Pad81)") (class "Default")
      (node (ref "U3") (pin "81") (pinfunction "PTB17_81") (pintype "passive"))
    )
    (net (code "111") (name "unconnected-(U3-PTC0-Pad90)") (class "Default")
      (node (ref "U3") (pin "90") (pinfunction "PTC0_90") (pintype "passive"))
    )
    (net (code "112") (name "unconnected-(U3-PTC1-Pad89)") (class "Default")
      (node (ref "U3") (pin "89") (pinfunction "PTC1_89") (pintype "passive"))
    )
    (net (code "113") (name "unconnected-(U3-PTC2-Pad92)") (class "Default")
      (node (ref "U3") (pin "92") (pinfunction "PTC2_92") (pintype "passive"))
    )
    (net (code "114") (name "unconnected-(U3-PTC8-Pad98)") (class "Default")
      (node (ref "U3") (pin "98") (pinfunction "PTC8_98") (pintype "passive"))
    )
    (net (code "115") (name "unconnected-(U3-PTC9-Pad97)") (class "Default")
      (node (ref "U3") (pin "97") (pinfunction "PTC9_97") (pintype "passive"))
    )
    (net (code "116") (name "unconnected-(U3-PTC12-Pad102)") (class "Default")
      (node (ref "U3") (pin "102") (pinfunction "PTC12_102") (pintype "passive"))
    )
    (net (code "117") (name "unconnected-(U3-PTC13-Pad101)") (class "Default")
      (node (ref "U3") (pin "101") (pinfunction "PTC13_101") (pintype "passive"))
    )
    (net (code "118") (name "unconnected-(U3-PTC14-Pad104)") (class "Default")
      (node (ref "U3") (pin "104") (pinfunction "PTC14_104") (pintype "passive"))
    )
    (net (code "119") (name "unconnected-(U3-PTC15-Pad103)") (class "Default")
      (node (ref "U3") (pin "103") (pinfunction "PTC15_103") (pintype "passive"))
    )
    (net (code "120") (name "unconnected-(U3-PTC16-Pad106)") (class "Default")
      (node (ref "U3") (pin "106") (pinfunction "PTC16_106") (pintype "passive"))
    )
    (net (code "121") (name "unconnected-(U3-PTC17-Pad105)") (class "Default")
      (node (ref "U3") (pin "105") (pinfunction "PTC17_105") (pintype "passive"))
    )
    (net (code "122") (name "unconnected-(U3-PTC18-Pad108)") (class "Default")
      (node (ref "U3") (pin "108") (pinfunction "PTC18_108") (pintype "passive"))
    )
    (net (code "123") (name "unconnected-(U3-PTC19-Pad107)") (class "Default")
      (node (ref "U3") (pin "107") (pinfunction "PTC19_107") (pintype "passive"))
    )
    (net (code "124") (name "unconnected-(U3-PTD0-Pad110)") (class "Default")
      (node (ref "U3") (pin "110") (pinfunction "PTD0_110") (pintype "passive"))
    )
    (net (code "125") (name "unconnected-(U3-PTD1-Pad109)") (class "Default")
      (node (ref "U3") (pin "109") (pinfunction "PTD1_109") (pintype "passive"))
    )
    (net (code "126") (name "unconnected-(U3-PTD2-Pad112)") (class "Default")
      (node (ref "U3") (pin "112") (pinfunction "PTD2_112") (pintype "passive"))
    )
    (net (code "127") (name "unconnected-(U3-PTD3-Pad111)") (class "Default")
      (node (ref "U3") (pin "111") (pinfunction "PTD3_111") (pintype "passive"))
    )
    (net (code "128") (name "unconnected-(U3-PTD7-Pad115)") (class "Default")
      (node (ref "U3") (pin "115") (pinfunction "PTD7_115") (pintype "passive"))
    )
    (net (code "129") (name "unconnected-(U3-PTD9-Pad117)") (class "Default")
      (node (ref "U3") (pin "117") (pinfunction "PTD9_117") (pintype "passive"))
    )
    (net (code "130") (name "unconnected-(U3-PTD10-Pad120)") (class "Default")
      (node (ref "U3") (pin "120") (pinfunction "PTD10_120") (pintype "passive"))
    )
    (net (code "131") (name "unconnected-(U3-PTD11-Pad119)") (class "Default")
      (node (ref "U3") (pin "119") (pinfunction "PTD11_119") (pintype "passive"))
    )
    (net (code "132") (name "unconnected-(U3-PTD12-Pad122)") (class "Default")
      (node (ref "U3") (pin "122") (pinfunction "PTD12_122") (pintype "passive"))
    )
    (net (code "133") (name "unconnected-(U3-PTD13-Pad121)") (class "Default")
      (node (ref "U3") (pin "121") (pinfunction "PTD13_121") (pintype "passive"))
    )
    (net (code "134") (name "unconnected-(U3-PTD14-Pad124)") (class "Default")
      (node (ref "U3") (pin "124") (pinfunction "PTD14_124") (pintype "passive"))
    )
    (net (code "135") (name "unconnected-(U3-PTD15-Pad123)") (class "Default")
      (node (ref "U3") (pin "123") (pinfunction "PTD15_123") (pintype "passive"))
    )
    (net (code "136") (name "unconnected-(U3-PTE6-Pad7)") (class "Default")
      (node (ref "U3") (pin "7") (pinfunction "PTE6_7") (pintype "passive"))
    )
    (net (code "137") (name "unconnected-(U3-PTE7-Pad8)") (class "Default")
      (node (ref "U3") (pin "8") (pinfunction "PTE7_8") (pintype "passive"))
    )
    (net (code "138") (name "unconnected-(U3-PTE8-Pad9)") (class "Default")
      (node (ref "U3") (pin "9") (pinfunction "PTE8_9") (pintype "passive"))
    )
    (net (code "139") (name "unconnected-(U3-PTE9-Pad10)") (class "Default")
      (node (ref "U3") (pin "10") (pinfunction "PTE9_10") (pintype "passive"))
    )
    (net (code "140") (name "unconnected-(U3-PTE11-Pad12)") (class "Default")
      (node (ref "U3") (pin "12") (pinfunction "PTE11_12") (pintype "passive"))
    )
    (net (code "141") (name "unconnected-(U3-PTE24-Pad32)") (class "Default")
      (node (ref "U3") (pin "32") (pinfunction "PTE24_32") (pintype "passive"))
    )
    (net (code "142") (name "unconnected-(U3-PTE25-Pad33)") (class "Default")
      (node (ref "U3") (pin "33") (pinfunction "PTE25_33") (pintype "passive"))
    )
    (net (code "143") (name "unconnected-(U3-PTE26-Pad34)") (class "Default")
      (node (ref "U3") (pin "34") (pinfunction "PTE26_34") (pintype "passive"))
    )
    (net (code "144") (name "unconnected-(U3-PTE28-Pad36)") (class "Default")
      (node (ref "U3") (pin "36") (pinfunction "PTE28_36") (pintype "passive"))
    )
    (net (code "145") (name "unconnected-(U3-RESET-Pad38)") (class "Default")
      (node (ref "U3") (pin "38") (pinfunction "RESET_38") (pintype "passive"))
    )
    (net (code "146") (name "unconnected-(U3-USB0_DM-Pad15)") (class "Default")
      (node (ref "U3") (pin "15") (pinfunction "USB0_DM_15") (pintype "passive"))
    )
    (net (code "147") (name "unconnected-(U3-USB0_DP-Pad14)") (class "Default")
      (node (ref "U3") (pin "14") (pinfunction "USB0_DP_14") (pintype "passive"))
    )
    (net (code "148") (name "unconnected-(U3-VREFH-Pad25)") (class "Default")
      (node (ref "U3") (pin "25") (pinfunction "VREFH_25") (pintype "passive"))
    )
    (net (code "149") (name "unconnected-(U3-VREGIN-Pad16)") (class "Default")
      (node (ref "U3") (pin "16") (pinfunction "VREGIN_16") (pintype "passive"))
    )
    (net (code "150") (name "unconnected-(U4-~{RESET}-Pad8)") (class "Default")
      (node (ref "U4") (pin "8") (pinfunction "~{RESET}_8") (pintype "passive"))
    )
  )
)
